# board_UNIVERSAL.net
KiCad netlist of a schematic drawn in EAGLE
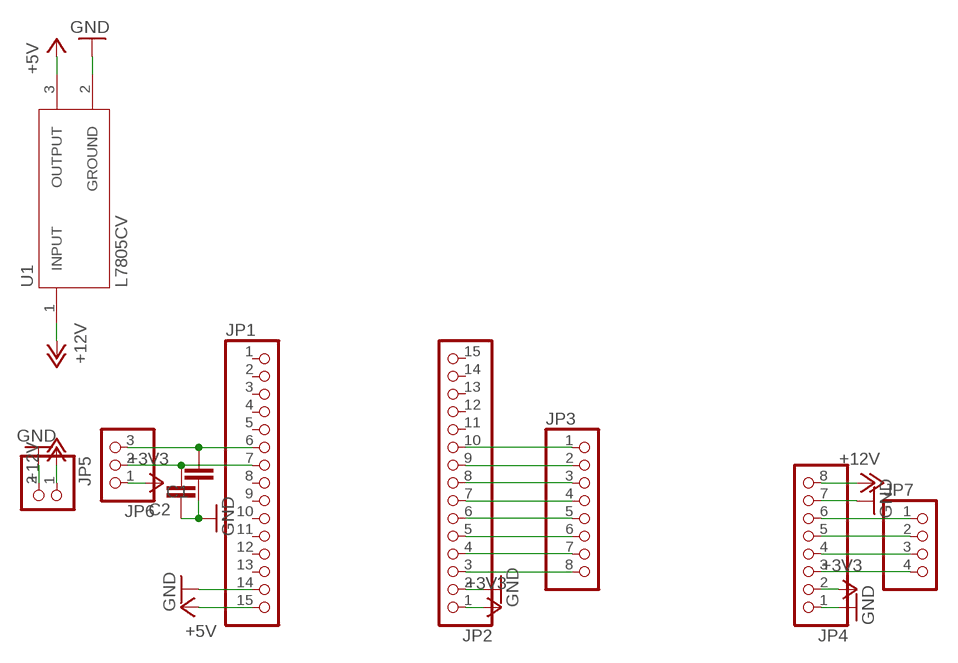
[diagram p0: schematic, sheet 1]

(export (version "E")
  (design (tool "Eeschema 10.0.6"))
  (components
    (comp (ref "C1")
      (value "C-EU025-030X050")
      (footprint "eagle-import:C025-030X050")
      (libsource (lib "eagle-import") (part "C-EU025-030X050"))
    )
    (comp (ref "C2")
      (value "C-EU025-030X050")
      (footprint "eagle-import:C025-030X050")
      (libsource (lib "eagle-import") (part "C-EU025-030X050"))
    )
    (comp (ref "JP1")
      (value "PINHD-1X15")
      (footprint "eagle-import:1X15")
      (libsource (lib "eagle-import") (part "PINHD-1X15"))
    )
    (comp (ref "JP2")
      (value "PINHD-1X15")
      (footprint "eagle-import:1X15")
      (libsource (lib "eagle-import") (part "PINHD-1X15"))
    )
    (comp (ref "JP3")
      (value "PINHD-1X8")
      (footprint "eagle-import:1X08")
      (libsource (lib "eagle-import") (part "PINHD-1X8"))
    )
    (comp (ref "JP4")
      (value "PINHD-1X8")
      (footprint "eagle-import:1X08")
      (libsource (lib "eagle-import") (part "PINHD-1X8"))
    )
    (comp (ref "JP5")
      (value "PINHD-1X2")
      (footprint "eagle-import:1X02")
      (libsource (lib "eagle-import") (part "PINHD-1X2"))
    )
    (comp (ref "JP6")
      (value "PINHD-1X3")
      (footprint "eagle-import:1X03")
      (libsource (lib "eagle-import") (part "PINHD-1X3"))
    )
    (comp (ref "JP7")
      (value "PINHD-1X4")
      (footprint "eagle-import:1X04")
      (libsource (lib "eagle-import") (part "PINHD-1X4"))
    )
    (comp (ref "U1")
      (value "L7805CV")
      (footprint "eagle-import:TO255P1040X460X1968-3")
      (fields (field (name "MF") "STMicroelectronics"))
      (libsource (lib "eagle-import") (part "L7805CV"))
    )
  )
  (nets
    (net (code "1") (name "+3V3") (class "Default")
      (node (ref "JP2") (pin "1") (pinfunction "1_1") (pintype "passive"))
      (node (ref "JP4") (pin "2") (pinfunction "2_2") (pintype "passive"))
      (node (ref "JP6") (pin "1") (pinfunction "1_1") (pintype "passive"))
    )
    (net (code "2") (name "+5V") (class "Default")
      (node (ref "JP1") (pin "15") (pinfunction "15_15") (pintype "passive"))
      (node (ref "U1") (pin "3") (pinfunction "OUTPUT_3") (pintype "output"))
    )
    (net (code "3") (name "+12V") (class "Default")
      (node (ref "JP4") (pin "8") (pinfunction "8_8") (pintype "passive"))
      (node (ref "JP5") (pin "1") (pinfunction "1_1") (pintype "passive"))
      (node (ref "U1") (pin "1") (pinfunction "INPUT_1") (pintype "input"))
    )
    (net (code "4") (name "GND") (class "Default")
      (node (ref "C1") (pin "1") (pinfunction "1_1") (pintype "passive"))
      (node (ref "C2") (pin "1") (pinfunction "1_1") (pintype "passive"))
      (node (ref "JP1") (pin "14") (pinfunction "14_14") (pintype "passive"))
      (node (ref "JP2") (pin "2") (pinfunction "2_2") (pintype "passive"))
      (node (ref "JP4") (pin "1") (pinfunction "1_1") (pintype "passive"))
      (node (ref "JP4") (pin "7") (pinfunction "7_7") (pintype "passive"))
      (node (ref "JP5") (pin "2") (pinfunction "2_2") (pintype "passive"))
      (node (ref "U1") (pin "2") (pinfunction "GROUND_2") (pintype "power_in"))
    )
    (net (code "5") (name "Net-(C1-Pad2)") (class "Default")
      (node (ref "C1") (pin "2") (pinfunction "2_2") (pintype "passive"))
      (node (ref "JP1") (pin "6") (pinfunction "6_6") (pintype "passive"))
      (node (ref "JP6") (pin "3") (pinfunction "3_3") (pintype "passive"))
    )
    (net (code "6") (name "Net-(C2-Pad2)") (class "Default")
      (node (ref "C2") (pin "2") (pinfunction "2_2") (pintype "passive"))
      (node (ref "JP1") (pin "7") (pinfunction "7_7") (pintype "passive"))
      (node (ref "JP6") (pin "2") (pinfunction "2_2") (pintype "passive"))
    )
    (net (code "7") (name "Net-(JP2-Pad3)") (class "Default")
      (node (ref "JP2") (pin "3") (pinfunction "3_3") (pintype "passive"))
      (node (ref "JP3") (pin "8") (pinfunction "8_8") (pintype "passive"))
    )
    (net (code "8") (name "Net-(JP2-Pad4)") (class "Default")
      (node (ref "JP2") (pin "4") (pinfunction "4_4") (pintype "passive"))
      (node (ref "JP3") (pin "7") (pinfunction "7_7") (pintype "passive"))
    )
    (net (code "9") (name "Net-(JP2-Pad5)") (class "Default")
      (node (ref "JP2") (pin "5") (pinfunction "5_5") (pintype "passive"))
      (node (ref "JP3") (pin "6") (pinfunction "6_6") (pintype "passive"))
    )
    (net (code "10") (name "Net-(JP2-Pad6)") (class "Default")
      (node (ref "JP2") (pin "6") (pinfunction "6_6") (pintype "passive"))
      (node (ref "JP3") (pin "5") (pinfunction "5_5") (pintype "passive"))
    )
    (net (code "11") (name "Net-(JP2-Pad7)") (class "Default")
      (node (ref "JP2") (pin "7") (pinfunction "7_7") (pintype "passive"))
      (node (ref "JP3") (pin "4") (pinfunction "4_4") (pintype "passive"))
    )
    (net (code "12") (name "Net-(JP2-Pad8)") (class "Default")
      (node (ref "JP2") (pin "8") (pinfunction "8_8") (pintype "passive"))
      (node (ref "JP3") (pin "3") (pinfunction "3_3") (pintype "passive"))
    )
    (net (code "13") (name "Net-(JP2-Pad9)") (class "Default")
      (node (ref "JP2") (pin "9") (pinfunction "9_9") (pintype "passive"))
      (node (ref "JP3") (pin "2") (pinfunction "2_2") (pintype "passive"))
    )
    (net (code "14") (name "Net-(JP2-Pad10)") (class "Default")
      (node (ref "JP2") (pin "10") (pinfunction "10_10") (pintype "passive"))
      (node (ref "JP3") (pin "1") (pinfunction "1_1") (pintype "passive"))
    )
    (net (code "15") (name "Net-(JP4-Pad3)") (class "Default")
      (node (ref "JP4") (pin "3") (pinfunction "3_3") (pintype "passive"))
      (node (ref "JP7") (pin "4") (pinfunction "4_4") (pintype "passive"))
    )
    (net (code "16") (name "Net-(JP4-Pad4)") (class "Default")
      (node (ref "JP4") (pin "4") (pinfunction "4_4") (pintype "passive"))
      (node (ref "JP7") (pin "3") (pinfunction "3_3") (pintype "passive"))
    )
    (net (code "17") (name "Net-(JP4-Pad5)") (class "Default")
      (node (ref "JP4") (pin "5") (pinfunction "5_5") (pintype "passive"))
      (node (ref "JP7") (pin "2") (pinfunction "2_2") (pintype "passive"))
    )
    (net (code "18") (name "Net-(JP4-Pad6)") (class "Default")
      (node (ref "JP4") (pin "6") (pinfunction "6_6") (pintype "passive"))
      (node (ref "JP7") (pin "1") (pinfunction "1_1") (pintype "passive"))
    )
    (net (code "19") (name "unconnected-(JP1-Pad1)") (class "Default")
      (node (ref "JP1") (pin "1") (pinfunction "1_1") (pintype "passive"))
    )
    (net (code "20") (name "unconnected-(JP1-Pad2)") (class "Default")
      (node (ref "JP1") (pin "2") (pinfunction "2_2") (pintype "passive"))
    )
    (net (code "21") (name "unconnected-(JP1-Pad3)") (class "Default")
      (node (ref "JP1") (pin "3") (pinfunction "3_3") (pintype "passive"))
    )
    (net (code "22") (name "unconnected-(JP1-Pad4)") (class "Default")
      (node (ref "JP1") (pin "4") (pinfunction "4_4") (pintype "passive"))
    )
    (net (code "23") (name "unconnected-(JP1-Pad5)") (class "Default")
      (node (ref "JP1") (pin "5") (pinfunction "5_5") (pintype "passive"))
    )
    (net (code "24") (name "unconnected-(JP1-Pad8)") (class "Default")
      (node (ref "JP1") (pin "8") (pinfunction "8_8") (pintype "passive"))
    )
    (net (code "25") (name "unconnected-(JP1-Pad9)") (class "Default")
      (node (ref "JP1") (pin "9") (pinfunction "9_9") (pintype "passive"))
    )
    (net (code "26") (name "unconnected-(JP1-Pad10)") (class "Default")
      (node (ref "JP1") (pin "10") (pinfunction "10_10") (pintype "passive"))
    )
    (net (code "27") (name "unconnected-(JP1-Pad11)") (class "Default")
      (node (ref "JP1") (pin "11") (pinfunction "11_11") (pintype "passive"))
    )
    (net (code "28") (name "unconnected-(JP1-Pad12)") (class "Default")
      (node (ref "JP1") (pin "12") (pinfunction "12_12") (pintype "passive"))
    )
    (net (code "29") (name "unconnected-(JP1-Pad13)") (class "Default")
      (node (ref "JP1") (pin "13") (pinfunction "13_13") (pintype "passive"))
    )
    (net (code "30") (name "unconnected-(JP2-Pad11)") (class "Default")
      (node (ref "JP2") (pin "11") (pinfunction "11_11") (pintype "passive"))
    )
    (net (code "31") (name "unconnected-(JP2-Pad12)") (class "Default")
      (node (ref "JP2") (pin "12") (pinfunction "12_12") (pintype "passive"))
    )
    (net (code "32") (name "unconnected-(JP2-Pad13)") (class "Default")
      (node (ref "JP2") (pin "13") (pinfunction "13_13") (pintype "passive"))
    )
    (net (code "33") (name "unconnected-(JP2-Pad14)") (class "Default")
      (node (ref "JP2") (pin "14") (pinfunction "14_14") (pintype "passive"))
    )
    (net (code "34") (name "unconnected-(JP2-Pad15)") (class "Default")
      (node (ref "JP2") (pin "15") (pinfunction "15_15") (pintype "passive"))
    )
  )
)
